# DI_DO_AI_AO.net
KiCad netlist of a schematic drawn in Altium Designer
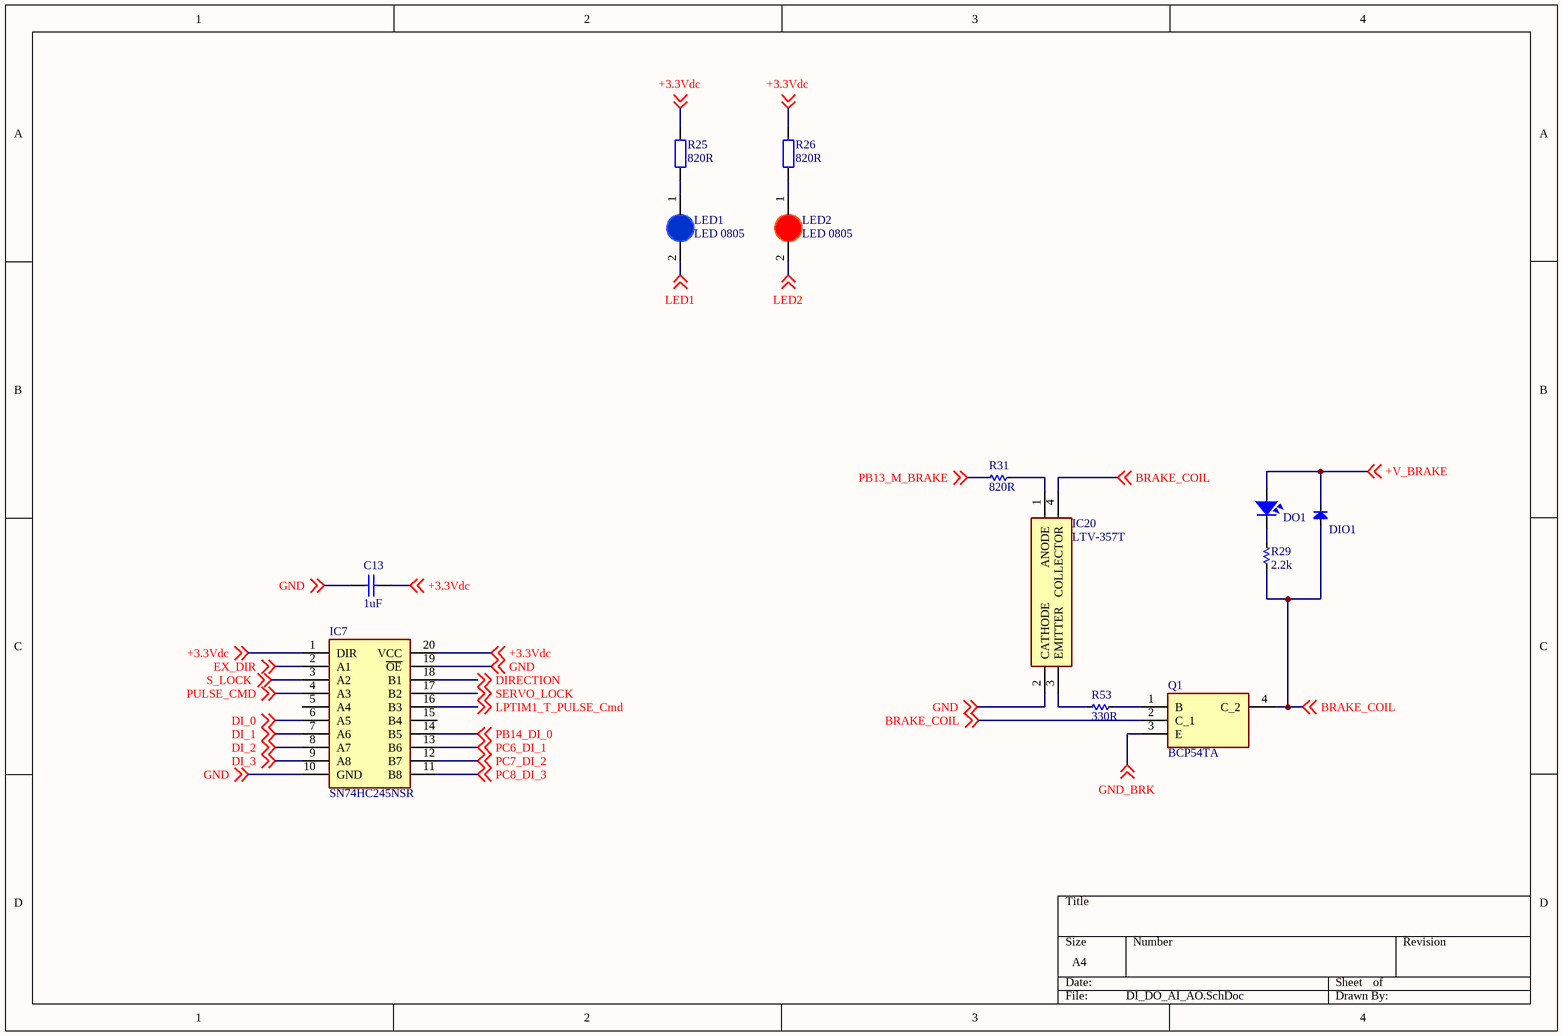
[diagram p0: DI_DO_AI_AO.SchDoc]

(export (version "E")
  (design (tool "Eeschema 10.0.6"))
  (components
    (comp (ref "C13")
      (value "1uF")
      (footprint "tu 0805")
      (description "Dán")
      (libsource (lib "Tu dien") (part "Tu 0805 10pF 50V 10%"))
    )
    (comp (ref "DIO1")
      (value "Diode SMD")
      (footprint "DIO-SMD-106")
      (description "Default Diode")
      (fields (field (name "PUBLISHER") "Altium Limited"))
      (libsource (lib "LIBRARY") (part "Diode SMD"))
    )
    (comp (ref "DO1")
      (value "LED")
      (footprint "LED-0805-Yellow")
      (libsource (lib "LIBRARY") (part "LED SMD"))
    )
    (comp (ref "IC7")
      (value "SN74HC245NSR")
      (footprint "SamacSys:SOIC127P780X200-20N")
      (description "Integrated Circuit")
      (fields (field (name "MOUSER PART NUMBER") "595-SN74HC245NSR"))
      (libsource (lib "*") (part "SN74HC245NSR"))
    )
    (comp (ref "IC20")
      (value "LTV-357T")
      (footprint "LTV-357T")
      (description "Integrated Circuit")
      (fields (field (name "MOUSER PART NUMBER") "859-LTV-357T"))
      (libsource (lib "SamacSys") (part "LTV-357T"))
    )
    (comp (ref "LED1")
      (value "LED 0805")
      (footprint "LED-0805-Blue")
      (description "Dán")
      (libsource (lib "Led") (part "LED 0805 Xanh Duong"))
    )
    (comp (ref "LED2")
      (value "LED 0805")
      (footprint "LED-0805-Red")
      (description "Dán")
      (libsource (lib "Led") (part "LED 0805 Do"))
    )
    (comp (ref "Q1")
      (value "BCP54TA")
      (footprint "SamacSys:SOT230P700X165-4N")
      (description "Transistor BJT NPN")
      (fields (field (name "MOUSER PART NUMBER") "522-BCP54TA"))
      (libsource (lib "SamacSys") (part "BCP54TA"))
    )
    (comp (ref "R25")
      (value "820R")
      (footprint "tro smd 0805")
      (description "Dán")
      (libsource (lib "Dien Tro") (part "Tro 0805 1% 2k"))
    )
    (comp (ref "R26")
      (value "820R")
      (footprint "tro smd 0805")
      (description "Dán")
      (libsource (lib "Dien Tro") (part "Tro 0805 1% 2k"))
    )
    (comp (ref "R29")
      (value "2.2k")
      (footprint "RES-SMD-0805")
      (description "Resistor")
      (fields
        (field (name "MANUFACTURER") "Generic Components")
        (field (name "PUBLISHER") "Altium Hobart Technology Centre")
      )
      (libsource (lib "LIBRARY") (part "Res-SMD"))
    )
    (comp (ref "R31")
      (value "820R")
      (footprint "RES-SMD-0805")
      (description "Resistor")
      (fields
        (field (name "MANUFACTURER") "Generic Components")
        (field (name "PUBLISHER") "Altium Hobart Technology Centre")
      )
      (libsource (lib "LIBRARY") (part "Res-SMD"))
    )
    (comp (ref "R53")
      (value "330R")
      (footprint "RES-SMD-0805")
      (description "Resistor")
      (fields
        (field (name "MANUFACTURER") "Generic Components")
        (field (name "PUBLISHER") "Altium Hobart Technology Centre")
      )
      (libsource (lib "LIBRARY") (part "Res-SMD"))
    )
  )
  (nets
    (net (code "1") (name "+3.3Vdc") (class "Default")
      (node (ref "C13") (pin "1") (pinfunction "1_1") (pintype "passive"))
      (node (ref "IC7") (pin "1") (pinfunction "DIR_1") (pintype "passive"))
      (node (ref "IC7") (pin "20") (pinfunction "VCC_20") (pintype "passive"))
      (node (ref "R25") (pin "2") (pinfunction "2_2") (pintype "passive"))
      (node (ref "R26") (pin "2") (pinfunction "2_2") (pintype "passive"))
    )
    (net (code "2") (name "+V_BRAKE") (class "Default")
      (node (ref "DIO1") (pin "2") (pinfunction "K_2") (pintype "passive"))
      (node (ref "DO1") (pin "1") (pinfunction "1_1") (pintype "passive"))
    )
    (net (code "3") (name "BRAKE_COIL") (class "Default")
      (node (ref "DIO1") (pin "1") (pinfunction "A_1") (pintype "passive"))
      (node (ref "IC20") (pin "4") (pinfunction "COLLECTOR_4") (pintype "passive"))
      (node (ref "Q1") (pin "2") (pinfunction "C_1_2") (pintype "passive"))
      (node (ref "Q1") (pin "4") (pinfunction "C_2_4") (pintype "passive"))
      (node (ref "R29") (pin "2") (pinfunction "2_2") (pintype "passive"))
    )
    (net (code "4") (name "DIRECTION") (class "Default")
      (node (ref "IC7") (pin "18") (pinfunction "B1_18") (pintype "passive"))
    )
    (net (code "5") (name "DI_0") (class "Default")
      (node (ref "IC7") (pin "6") (pinfunction "A5_6") (pintype "passive"))
    )
    (net (code "6") (name "DI_1") (class "Default")
      (node (ref "IC7") (pin "7") (pinfunction "A6_7") (pintype "passive"))
    )
    (net (code "7") (name "DI_2") (class "Default")
      (node (ref "IC7") (pin "8") (pinfunction "A7_8") (pintype "passive"))
    )
    (net (code "8") (name "DI_3") (class "Default")
      (node (ref "IC7") (pin "9") (pinfunction "A8_9") (pintype "passive"))
    )
    (net (code "9") (name "EX_DIR") (class "Default")
      (node (ref "IC7") (pin "2") (pinfunction "A1_2") (pintype "passive"))
    )
    (net (code "10") (name "GND") (class "Default")
      (node (ref "C13") (pin "2") (pinfunction "2_2") (pintype "passive"))
      (node (ref "IC20") (pin "2") (pinfunction "CATHODE_2") (pintype "passive"))
      (node (ref "IC7") (pin "10") (pinfunction "GND_10") (pintype "passive"))
      (node (ref "IC7") (pin "19") (pinfunction "~{OE}_19") (pintype "passive"))
    )
    (net (code "11") (name "GND_BRK") (class "Default")
      (node (ref "Q1") (pin "3") (pinfunction "E_3") (pintype "passive"))
    )
    (net (code "12") (name "LED1") (class "Default")
      (node (ref "LED1") (pin "2") (pinfunction "K_2") (pintype "passive"))
    )
    (net (code "13") (name "LED2") (class "Default")
      (node (ref "LED2") (pin "2") (pinfunction "K_2") (pintype "passive"))
    )
    (net (code "14") (name "LPTIM1_T_PULSE_Cmd") (class "Default")
      (node (ref "IC7") (pin "16") (pinfunction "B3_16") (pintype "passive"))
    )
    (net (code "15") (name "Net-(DO1-Pad2)") (class "Default")
      (node (ref "DO1") (pin "2") (pinfunction "2_2") (pintype "passive"))
      (node (ref "R29") (pin "1") (pinfunction "1_1") (pintype "passive"))
    )
    (net (code "16") (name "Net-(IC20-ANODE)") (class "Default")
      (node (ref "IC20") (pin "1") (pinfunction "ANODE_1") (pintype "passive"))
      (node (ref "R31") (pin "1") (pinfunction "1_1") (pintype "passive"))
    )
    (net (code "17") (name "Net-(IC20-EMITTER)") (class "Default")
      (node (ref "IC20") (pin "3") (pinfunction "EMITTER_3") (pintype "passive"))
      (node (ref "R53") (pin "2") (pinfunction "2_2") (pintype "passive"))
    )
    (net (code "18") (name "Net-(LED1-A)") (class "Default")
      (node (ref "LED1") (pin "1") (pinfunction "A_1") (pintype "passive"))
      (node (ref "R25") (pin "1") (pinfunction "1_1") (pintype "passive"))
    )
    (net (code "19") (name "Net-(LED2-A)") (class "Default")
      (node (ref "LED2") (pin "1") (pinfunction "A_1") (pintype "passive"))
      (node (ref "R26") (pin "1") (pinfunction "1_1") (pintype "passive"))
    )
    (net (code "20") (name "Net-(Q1-B)") (class "Default")
      (node (ref "Q1") (pin "1") (pinfunction "B_1") (pintype "passive"))
      (node (ref "R53") (pin "1") (pinfunction "1_1") (pintype "passive"))
    )
    (net (code "21") (name "PB13_M_BRAKE") (class "Default")
      (node (ref "R31") (pin "2") (pinfunction "2_2") (pintype "passive"))
    )
    (net (code "22") (name "PB14_DI_0") (class "Default")
      (node (ref "IC7") (pin "14") (pinfunction "B5_14") (pintype "passive"))
    )
    (net (code "23") (name "PC6_DI_1") (class "Default")
      (node (ref "IC7") (pin "13") (pinfunction "B6_13") (pintype "passive"))
    )
    (net (code "24") (name "PC7_DI_2") (class "Default")
      (node (ref "IC7") (pin "12") (pinfunction "B7_12") (pintype "passive"))
    )
    (net (code "25") (name "PC8_DI_3") (class "Default")
      (node (ref "IC7") (pin "11") (pinfunction "B8_11") (pintype "passive"))
    )
    (net (code "26") (name "PULSE_CMD") (class "Default")
      (node (ref "IC7") (pin "4") (pinfunction "A3_4") (pintype "passive"))
    )
    (net (code "27") (name "SERVO_LOCK") (class "Default")
      (node (ref "IC7") (pin "17") (pinfunction "B2_17") (pintype "passive"))
    )
    (net (code "28") (name "S_LOCK") (class "Default")
      (node (ref "IC7") (pin "3") (pinfunction "A2_3") (pintype "passive"))
    )
    (net (code "29") (name "unconnected-(IC7-A4-Pad5)") (class "Default")
      (node (ref "IC7") (pin "5") (pinfunction "A4_5") (pintype "passive"))
    )
    (net (code "30") (name "unconnected-(IC7-B4-Pad15)") (class "Default")
      (node (ref "IC7") (pin "15") (pinfunction "B4_15") (pintype "passive"))
    )
  )
)
